# supply.net
KiCad netlist of a schematic drawn in Altium Designer
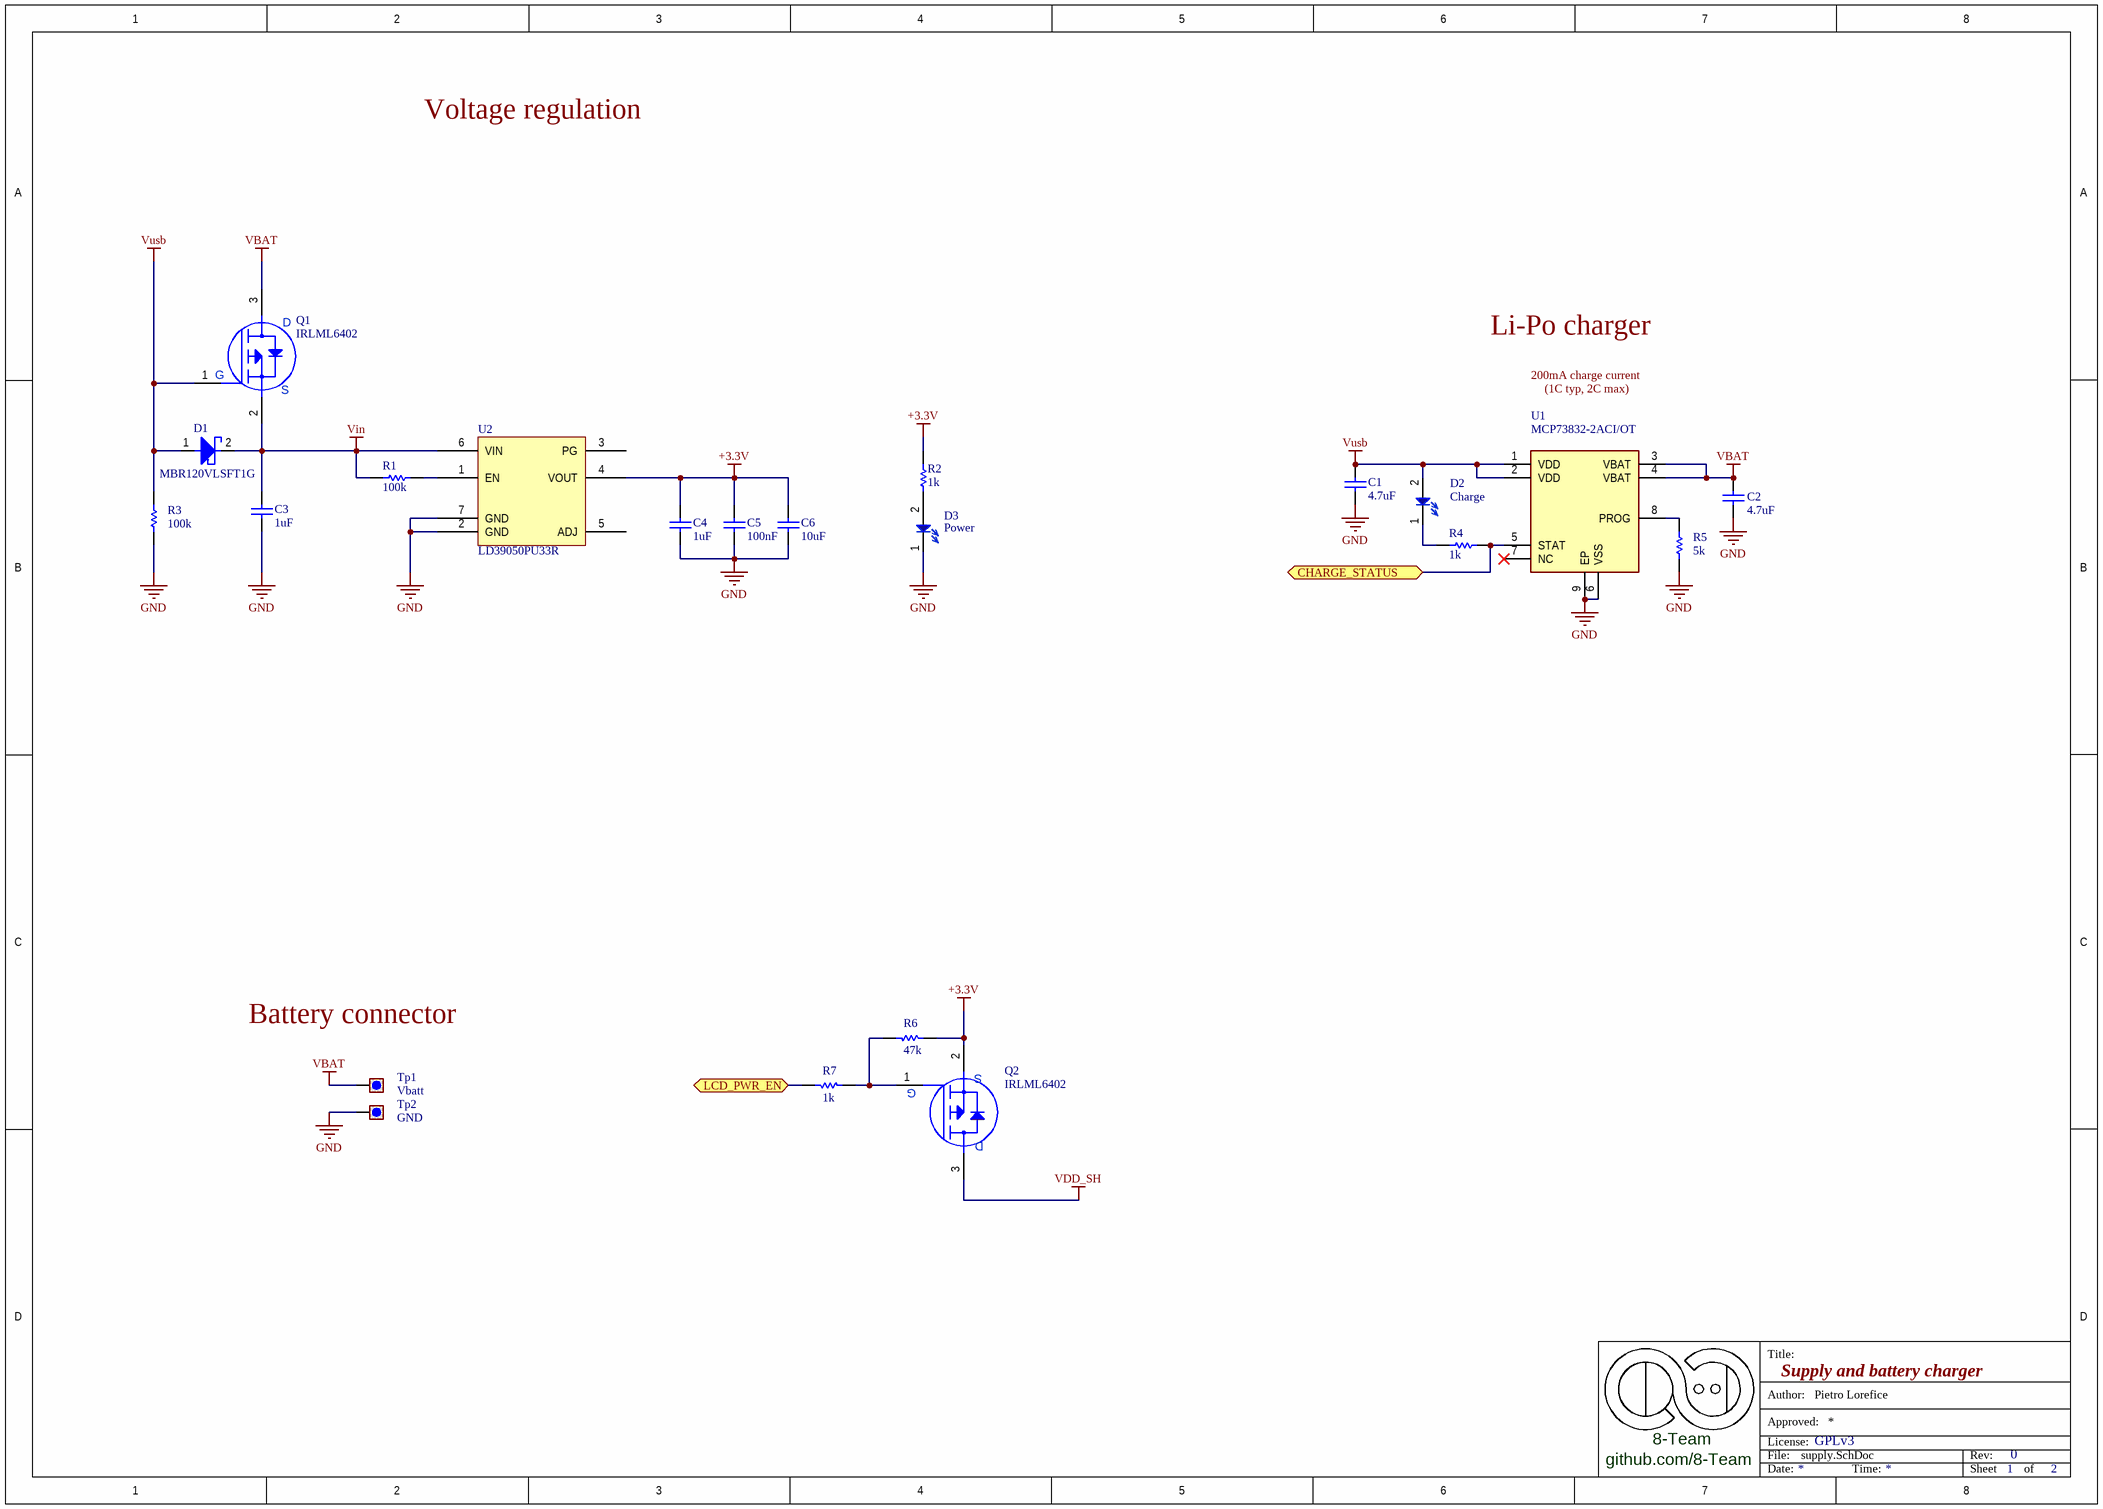
[diagram p0: supply.SchDoc]

(export (version "E")
  (design (tool "Eeschema 10.0.6"))
  (components
    (comp (ref "C1")
      (value "4.7uF")
      (footprint "0603_[1608]")
      (description "Capacitor")
      (fields (field (name "PUBLISHER") "Altium Limited"))
      (libsource (lib "Miscellaneous Devices") (part "Cap"))
    )
    (comp (ref "C2")
      (value "4.7uF")
      (footprint "0603_[1608]")
      (description "Capacitor")
      (fields (field (name "PUBLISHER") "Altium Limited"))
      (libsource (lib "Miscellaneous Devices") (part "Cap"))
    )
    (comp (ref "C3")
      (value "1uF")
      (footprint "0603_[1608]")
      (description "Capacitor")
      (fields (field (name "PUBLISHER") "Altium Limited"))
      (libsource (lib "Miscellaneous Devices") (part "Cap"))
    )
    (comp (ref "C4")
      (value "1uF")
      (footprint "0603_[1608]")
      (description "Capacitor")
      (fields (field (name "PUBLISHER") "Altium Limited"))
      (libsource (lib "Miscellaneous Devices") (part "Cap"))
    )
    (comp (ref "C5")
      (value "100nF")
      (footprint "0402_[1005]")
      (description "Capacitor")
      (fields (field (name "PUBLISHER") "Altium Limited"))
      (libsource (lib "Miscellaneous Devices") (part "Cap"))
    )
    (comp (ref "C6")
      (value "10uF")
      (footprint "0603_[1608]")
      (description "Capacitor")
      (fields (field (name "PUBLISHER") "Altium Limited"))
      (libsource (lib "Miscellaneous Devices") (part "Cap"))
    )
    (comp (ref "D1")
      (value "MBR120VLSFT1G")
      (footprint "SOD-123")
      (libsource (lib "develer_library") (part "Diode_SCHOTTKY"))
    )
    (comp (ref "D2")
      (value "Charge")
      (footprint "0402_[1005]_K1-A2_LED")
      (description "Red")
      (libsource (lib "develer_library") (part "LED_SMALL"))
    )
    (comp (ref "D3")
      (value "Power")
      (footprint "0402_[1005]_K1-A2_LED")
      (description "Green")
      (libsource (lib "develer_library") (part "LED_SMALL"))
    )
    (comp (ref "Q1")
      (value "IRLML6402")
      (footprint "SOT-23")
      (libsource (lib "develer_library") (part "MOSFET-P 3pin"))
    )
    (comp (ref "Q2")
      (value "IRLML6402")
      (footprint "SOT-23")
      (libsource (lib "develer_library") (part "MOSFET-P 3pin"))
    )
    (comp (ref "R1")
      (value "100k")
      (footprint "0402_[1005]")
      (description "Resistor")
      (fields (field (name "PUBLISHER") "Altium Limited"))
      (libsource (lib "Miscellaneous Devices") (part "Res1"))
    )
    (comp (ref "R2")
      (value "1k")
      (footprint "0402_[1005]")
      (description "Resistor")
      (fields (field (name "PUBLISHER") "Altium Limited"))
      (libsource (lib "Miscellaneous Devices") (part "Res1"))
    )
    (comp (ref "R3")
      (value "100k")
      (footprint "0402_[1005]")
      (description "Resistor")
      (fields (field (name "PUBLISHER") "Altium Limited"))
      (libsource (lib "Miscellaneous Devices") (part "Res1"))
    )
    (comp (ref "R4")
      (value "1k")
      (footprint "0402_[1005]")
      (description "Resistor")
      (fields (field (name "PUBLISHER") "Altium Limited"))
      (libsource (lib "Miscellaneous Devices") (part "Res1"))
    )
    (comp (ref "R5")
      (value "5k")
      (footprint "0402_[1005]")
      (description "Resistor")
      (fields (field (name "PUBLISHER") "Altium Limited"))
      (libsource (lib "Miscellaneous Devices") (part "Res1"))
    )
    (comp (ref "R6")
      (value "47k")
      (footprint "0402_[1005]")
      (description "Resistor")
      (fields (field (name "PUBLISHER") "Altium Limited"))
      (libsource (lib "DEVELER_Library") (part "Res1"))
    )
    (comp (ref "R7")
      (value "1k")
      (footprint "0402_[1005]")
      (description "Resistor")
      (fields (field (name "PUBLISHER") "Altium Limited"))
      (libsource (lib "DEVELER_Library") (part "Res1"))
    )
    (comp (ref "Tp1")
      (value "Vbatt")
      (footprint "TEST_POINT_SMD_D1.6MM")
      (libsource (lib "develer_library") (part "Test_point"))
    )
    (comp (ref "Tp2")
      (value "GND")
      (footprint "TEST_POINT_SMD_D1.6MM")
      (libsource (lib "develer_library") (part "Test_point"))
    )
    (comp (ref "U1")
      (value "MCP73832-2ACI/OT")
      (footprint "PQFN50P200X300X100_HS-9N")
      (description "Miniature Single-Cell, Fully Integrated Li-Ion, Li-Po Charge Management Controller")
      (libsource (lib "develer_library") (part "MCP7383x_DFN"))
    )
    (comp (ref "U2")
      (value "LD39050PU33R")
      (footprint "DFN95P300X300X100_HS-7L")
      (description "500mA low quiescent current and low noise voltage regulator")
      (libsource (lib "develer_library") (part "LD39050"))
    )
  )
  (nets
    (net (code "1") (name "+3.3V") (class "Default")
      (node (ref "C4") (pin "2") (pinfunction "2_2") (pintype "passive"))
      (node (ref "C5") (pin "2") (pinfunction "2_2") (pintype "passive"))
      (node (ref "C6") (pin "2") (pinfunction "2_2") (pintype "passive"))
      (node (ref "Q2") (pin "2") (pinfunction "S_2") (pintype "passive"))
      (node (ref "R2") (pin "1") (pinfunction "1_1") (pintype "passive"))
      (node (ref "R6") (pin "1") (pinfunction "1_1") (pintype "passive"))
      (node (ref "U2") (pin "4") (pinfunction "VOUT_4") (pintype "power_in"))
    )
    (net (code "2") (name "/CHARGE_STATUS") (class "Default")
      (node (ref "R4") (pin "2") (pinfunction "2_2") (pintype "passive"))
      (node (ref "U1") (pin "5") (pinfunction "STAT_5") (pintype "passive"))
    )
    (net (code "3") (name "/LCD_PWR_EN") (class "Default")
      (node (ref "R7") (pin "2") (pinfunction "2_2") (pintype "passive"))
    )
    (net (code "4") (name "GND") (class "Default")
      (node (ref "C1") (pin "1") (pinfunction "1_1") (pintype "passive"))
      (node (ref "C2") (pin "1") (pinfunction "1_1") (pintype "passive"))
      (node (ref "C3") (pin "2") (pinfunction "2_2") (pintype "passive"))
      (node (ref "C4") (pin "1") (pinfunction "1_1") (pintype "passive"))
      (node (ref "C5") (pin "1") (pinfunction "1_1") (pintype "passive"))
      (node (ref "C6") (pin "1") (pinfunction "1_1") (pintype "passive"))
      (node (ref "D3") (pin "1") (pinfunction "K_1") (pintype "passive"))
      (node (ref "R3") (pin "1") (pinfunction "1_1") (pintype "passive"))
      (node (ref "R5") (pin "1") (pinfunction "1_1") (pintype "passive"))
      (node (ref "Tp2") (pin "1") (pinfunction "1_1") (pintype "passive"))
      (node (ref "U1") (pin "6") (pinfunction "VSS_6") (pintype "power_in"))
      (node (ref "U1") (pin "9") (pinfunction "EP_9") (pintype "passive"))
      (node (ref "U2") (pin "2") (pinfunction "GND_2") (pintype "power_in"))
      (node (ref "U2") (pin "7") (pinfunction "GND_7") (pintype "power_in"))
    )
    (net (code "5") (name "Net-(D2-K)") (class "Default")
      (node (ref "D2") (pin "1") (pinfunction "K_1") (pintype "passive"))
      (node (ref "R4") (pin "1") (pinfunction "1_1") (pintype "passive"))
    )
    (net (code "6") (name "Net-(D3-A)") (class "Default")
      (node (ref "D3") (pin "2") (pinfunction "A_2") (pintype "passive"))
      (node (ref "R2") (pin "2") (pinfunction "2_2") (pintype "passive"))
    )
    (net (code "7") (name "Net-(Q2-G)") (class "Default")
      (node (ref "Q2") (pin "1") (pinfunction "G_1") (pintype "passive"))
      (node (ref "R6") (pin "2") (pinfunction "2_2") (pintype "passive"))
      (node (ref "R7") (pin "1") (pinfunction "1_1") (pintype "passive"))
    )
    (net (code "8") (name "Net-(U1-PROG)") (class "Default")
      (node (ref "R5") (pin "2") (pinfunction "2_2") (pintype "passive"))
      (node (ref "U1") (pin "8") (pinfunction "PROG_8") (pintype "passive"))
    )
    (net (code "9") (name "Net-(U2-EN)") (class "Default")
      (node (ref "R1") (pin "1") (pinfunction "1_1") (pintype "passive"))
      (node (ref "U2") (pin "1") (pinfunction "EN_1") (pintype "passive"))
    )
    (net (code "10") (name "VBAT") (class "Default")
      (node (ref "C2") (pin "2") (pinfunction "2_2") (pintype "passive"))
      (node (ref "Q1") (pin "3") (pinfunction "D_3") (pintype "passive"))
      (node (ref "Tp1") (pin "1") (pinfunction "1_1") (pintype "passive"))
      (node (ref "U1") (pin "3") (pinfunction "VBAT_3") (pintype "power_in"))
      (node (ref "U1") (pin "4") (pinfunction "VBAT_4") (pintype "power_in"))
    )
    (net (code "11") (name "VDD_SH") (class "Default")
      (node (ref "Q2") (pin "3") (pinfunction "D_3") (pintype "passive"))
    )
    (net (code "12") (name "Vin") (class "Default")
      (node (ref "C3") (pin "1") (pinfunction "1_1") (pintype "passive"))
      (node (ref "D1") (pin "2") (pinfunction "K_2") (pintype "passive"))
      (node (ref "Q1") (pin "2") (pinfunction "S_2") (pintype "passive"))
      (node (ref "R1") (pin "2") (pinfunction "2_2") (pintype "passive"))
      (node (ref "U2") (pin "6") (pinfunction "VIN_6") (pintype "power_in"))
    )
    (net (code "13") (name "Vusb") (class "Default")
      (node (ref "C1") (pin "2") (pinfunction "2_2") (pintype "passive"))
      (node (ref "D1") (pin "1") (pinfunction "A_1") (pintype "passive"))
      (node (ref "D2") (pin "2") (pinfunction "A_2") (pintype "passive"))
      (node (ref "Q1") (pin "1") (pinfunction "G_1") (pintype "passive"))
      (node (ref "R3") (pin "2") (pinfunction "2_2") (pintype "passive"))
      (node (ref "U1") (pin "1") (pinfunction "VDD_1") (pintype "power_in"))
      (node (ref "U1") (pin "2") (pinfunction "VDD_2") (pintype "power_in"))
    )
    (net (code "14") (name "unconnected-(U1-NC-Pad7)") (class "Default")
      (node (ref "U1") (pin "7") (pinfunction "NC_7") (pintype "passive+no_connect"))
    )
    (net (code "15") (name "unconnected-(U2-ADJ-Pad5)") (class "Default")
      (node (ref "U2") (pin "5") (pinfunction "ADJ_5") (pintype "passive"))
    )
    (net (code "16") (name "unconnected-(U2-PG-Pad3)") (class "Default")
      (node (ref "U2") (pin "3") (pinfunction "PG_3") (pintype "passive"))
    )
  )
)
